# modulo_cortina.net
KiCad netlist of a schematic drawn in EAGLE
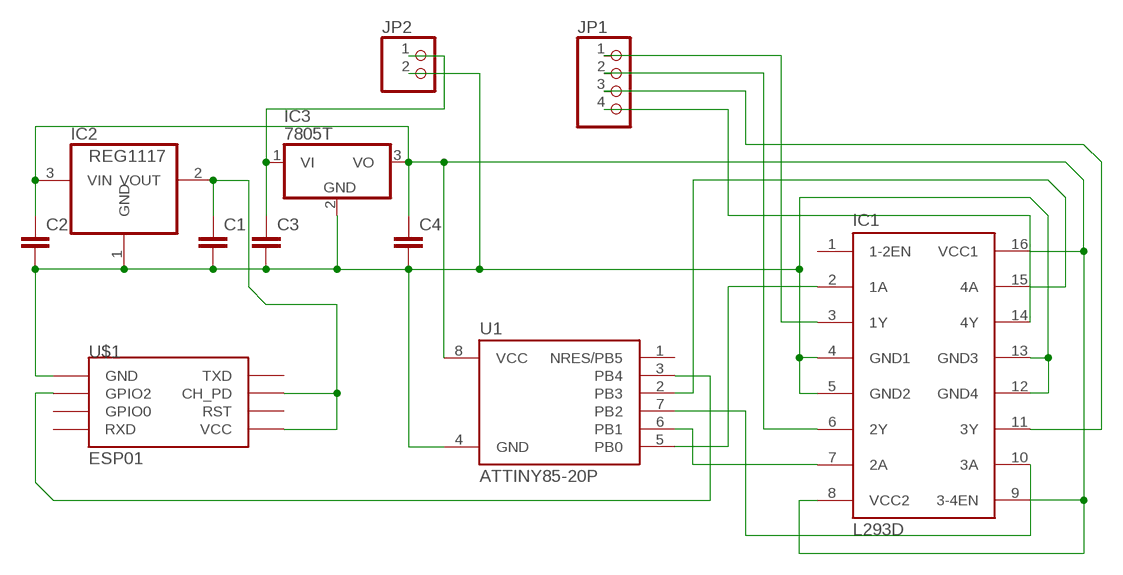
[diagram p0: schematic, sheet 1]

(export (version "E")
  (design (tool "Eeschema 10.0.6"))
  (components
    (comp (ref "C1")
      (value "C2,5-3")
      (footprint "eagle-import:C2.5-3")
      (libsource (lib "eagle-import") (part "C2,5-3"))
    )
    (comp (ref "C2")
      (value "C2,5-3")
      (footprint "eagle-import:C2.5-3")
      (libsource (lib "eagle-import") (part "C2,5-3"))
    )
    (comp (ref "C3")
      (value "C2,5-3")
      (footprint "eagle-import:C2.5-3")
      (libsource (lib "eagle-import") (part "C2,5-3"))
    )
    (comp (ref "C4")
      (value "C2,5-3")
      (footprint "eagle-import:C2.5-3")
      (libsource (lib "eagle-import") (part "C2,5-3"))
    )
    (comp (ref "IC1")
      (value "L293D")
      (footprint "eagle-import:DIL16")
      (libsource (lib "eagle-import") (part "L293D"))
    )
    (comp (ref "IC2")
      (value "REG1117")
      (footprint "eagle-import:SOT223")
      (libsource (lib "eagle-import") (part "REG1117"))
    )
    (comp (ref "IC3")
      (value "7805T")
      (footprint "eagle-import:TO220H")
      (libsource (lib "eagle-import") (part "78T05"))
    )
    (comp (ref "JP1")
      (value "PINHD-1X4")
      (footprint "eagle-import:1X04")
      (libsource (lib "eagle-import") (part "PINHD-1X4"))
    )
    (comp (ref "JP2")
      (value "PINHD-1X2")
      (footprint "eagle-import:1X02")
      (libsource (lib "eagle-import") (part "PINHD-1X2"))
    )
    (comp (ref "U$1")
      (value "ESP01")
      (footprint "eagle-import:ESP01")
      (libsource (lib "eagle-import") (part "ESP01"))
    )
    (comp (ref "U1")
      (value "ATTINY85-20P")
      (footprint "eagle-import:PDIP08_300MIL")
      (libsource (lib "eagle-import") (part "ATTINY85P-20"))
    )
  )
  (nets
    (net (code "1") (name "Net-(IC1-1A)") (class "Default")
      (node (ref "IC1") (pin "2") (pinfunction "1A_2") (pintype "input"))
      (node (ref "U1") (pin "5") (pinfunction "PB0_5") (pintype "bidirectional"))
    )
    (net (code "2") (name "Net-(IC1-1Y)") (class "Default")
      (node (ref "IC1") (pin "3") (pinfunction "1Y_3") (pintype "output"))
      (node (ref "JP1") (pin "1") (pinfunction "1_1") (pintype "passive"))
    )
    (net (code "3") (name "Net-(IC1-2A)") (class "Default")
      (node (ref "IC1") (pin "7") (pinfunction "2A_7") (pintype "input"))
      (node (ref "U1") (pin "6") (pinfunction "PB1_6") (pintype "bidirectional"))
    )
    (net (code "4") (name "Net-(IC1-2Y)") (class "Default")
      (node (ref "IC1") (pin "6") (pinfunction "2Y_6") (pintype "output"))
      (node (ref "JP1") (pin "2") (pinfunction "2_2") (pintype "passive"))
    )
    (net (code "5") (name "Net-(IC1-3-4EN)") (class "Default")
      (node (ref "C2") (pin "1") (pinfunction "1_1") (pintype "passive"))
      (node (ref "C4") (pin "1") (pinfunction "1_1") (pintype "passive"))
      (node (ref "IC1") (pin "16") (pinfunction "VCC1_16") (pintype "power_in"))
      (node (ref "IC1") (pin "8") (pinfunction "VCC2_8") (pintype "power_in"))
      (node (ref "IC1") (pin "9") (pinfunction "3-4EN_9") (pintype "input"))
      (node (ref "IC2") (pin "3") (pinfunction "VIN_3") (pintype "input"))
      (node (ref "IC3") (pin "3") (pinfunction "VO_3") (pintype "passive"))
      (node (ref "U1") (pin "8") (pinfunction "VCC_8") (pintype "power_in"))
    )
    (net (code "6") (name "Net-(IC1-3A)") (class "Default")
      (node (ref "IC1") (pin "10") (pinfunction "3A_10") (pintype "input"))
      (node (ref "U1") (pin "7") (pinfunction "PB2_7") (pintype "bidirectional"))
    )
    (net (code "7") (name "Net-(IC1-3Y)") (class "Default")
      (node (ref "IC1") (pin "11") (pinfunction "3Y_11") (pintype "output"))
      (node (ref "JP1") (pin "3") (pinfunction "3_3") (pintype "passive"))
    )
    (net (code "8") (name "Net-(IC1-4A)") (class "Default")
      (node (ref "IC1") (pin "15") (pinfunction "4A_15") (pintype "input"))
      (node (ref "U1") (pin "2") (pinfunction "PB3_2") (pintype "bidirectional"))
    )
    (net (code "9") (name "Net-(IC1-4Y)") (class "Default")
      (node (ref "IC1") (pin "14") (pinfunction "4Y_14") (pintype "output"))
      (node (ref "JP1") (pin "4") (pinfunction "4_4") (pintype "passive"))
    )
    (net (code "10") (name "Net-(IC1-GND1)") (class "Default")
      (node (ref "C1") (pin "2") (pinfunction "2_2") (pintype "passive"))
      (node (ref "C2") (pin "2") (pinfunction "2_2") (pintype "passive"))
      (node (ref "C3") (pin "2") (pinfunction "2_2") (pintype "passive"))
      (node (ref "C4") (pin "2") (pinfunction "2_2") (pintype "passive"))
      (node (ref "IC1") (pin "12") (pinfunction "GND4_12") (pintype "power_in"))
      (node (ref "IC1") (pin "13") (pinfunction "GND3_13") (pintype "power_in"))
      (node (ref "IC1") (pin "4") (pinfunction "GND1_4") (pintype "power_in"))
      (node (ref "IC1") (pin "5") (pinfunction "GND2_5") (pintype "power_in"))
      (node (ref "IC2") (pin "1") (pinfunction "GND_1") (pintype "power_in"))
      (node (ref "IC3") (pin "2") (pinfunction "GND_2") (pintype "passive"))
      (node (ref "JP2") (pin "2") (pinfunction "2_2") (pintype "passive"))
      (node (ref "U$1") (pin "GND") (pinfunction "GND_GND") (pintype "bidirectional"))
      (node (ref "U1") (pin "4") (pinfunction "GND_4") (pintype "power_in"))
    )
    (net (code "11") (name "Net-(IC2-VOUT)") (class "Default")
      (node (ref "C1") (pin "1") (pinfunction "1_1") (pintype "passive"))
      (node (ref "IC2") (pin "2") (pinfunction "VOUT_2") (pintype "output"))
      (node (ref "U$1") (pin "CH_PD") (pinfunction "CH_PD_CH_PD") (pintype "bidirectional"))
      (node (ref "U$1") (pin "VCC") (pinfunction "VCC_VCC") (pintype "bidirectional"))
    )
    (net (code "12") (name "Net-(IC3-VI)") (class "Default")
      (node (ref "C3") (pin "1") (pinfunction "1_1") (pintype "passive"))
      (node (ref "IC3") (pin "1") (pinfunction "VI_1") (pintype "input"))
      (node (ref "JP2") (pin "1") (pinfunction "1_1") (pintype "passive"))
    )
    (net (code "13") (name "Net-(U1-PB4)") (class "Default")
      (node (ref "U$1") (pin "GPIO2") (pinfunction "GPIO2_GPIO2") (pintype "bidirectional"))
      (node (ref "U1") (pin "3") (pinfunction "PB4_3") (pintype "bidirectional"))
    )
    (net (code "14") (name "unconnected-(IC1-1-2EN-Pad1)") (class "Default")
      (node (ref "IC1") (pin "1") (pinfunction "1-2EN_1") (pintype "input"))
    )
    (net (code "15") (name "unconnected-(U$1-PadGPIO0)") (class "Default")
      (node (ref "U$1") (pin "GPIO0") (pinfunction "GPIO0_GPIO0") (pintype "bidirectional"))
    )
    (net (code "16") (name "unconnected-(U$1-PadRST)") (class "Default")
      (node (ref "U$1") (pin "RST") (pinfunction "RST_RST") (pintype "bidirectional"))
    )
    (net (code "17") (name "unconnected-(U$1-RXD-PadRX)") (class "Default")
      (node (ref "U$1") (pin "RX") (pinfunction "RXD_RX") (pintype "bidirectional"))
    )
    (net (code "18") (name "unconnected-(U$1-TXD-PadTX)") (class "Default")
      (node (ref "U$1") (pin "TX") (pinfunction "TXD_TX") (pintype "bidirectional"))
    )
    (net (code "19") (name "unconnected-(U1-NRES{slash}PB5-Pad1)") (class "Default")
      (node (ref "U1") (pin "1") (pinfunction "NRES/PB5_1") (pintype "bidirectional"))
    )
  )
)
